# Jlink_V9.net
KiCad netlist of a schematic drawn in Altium Designer
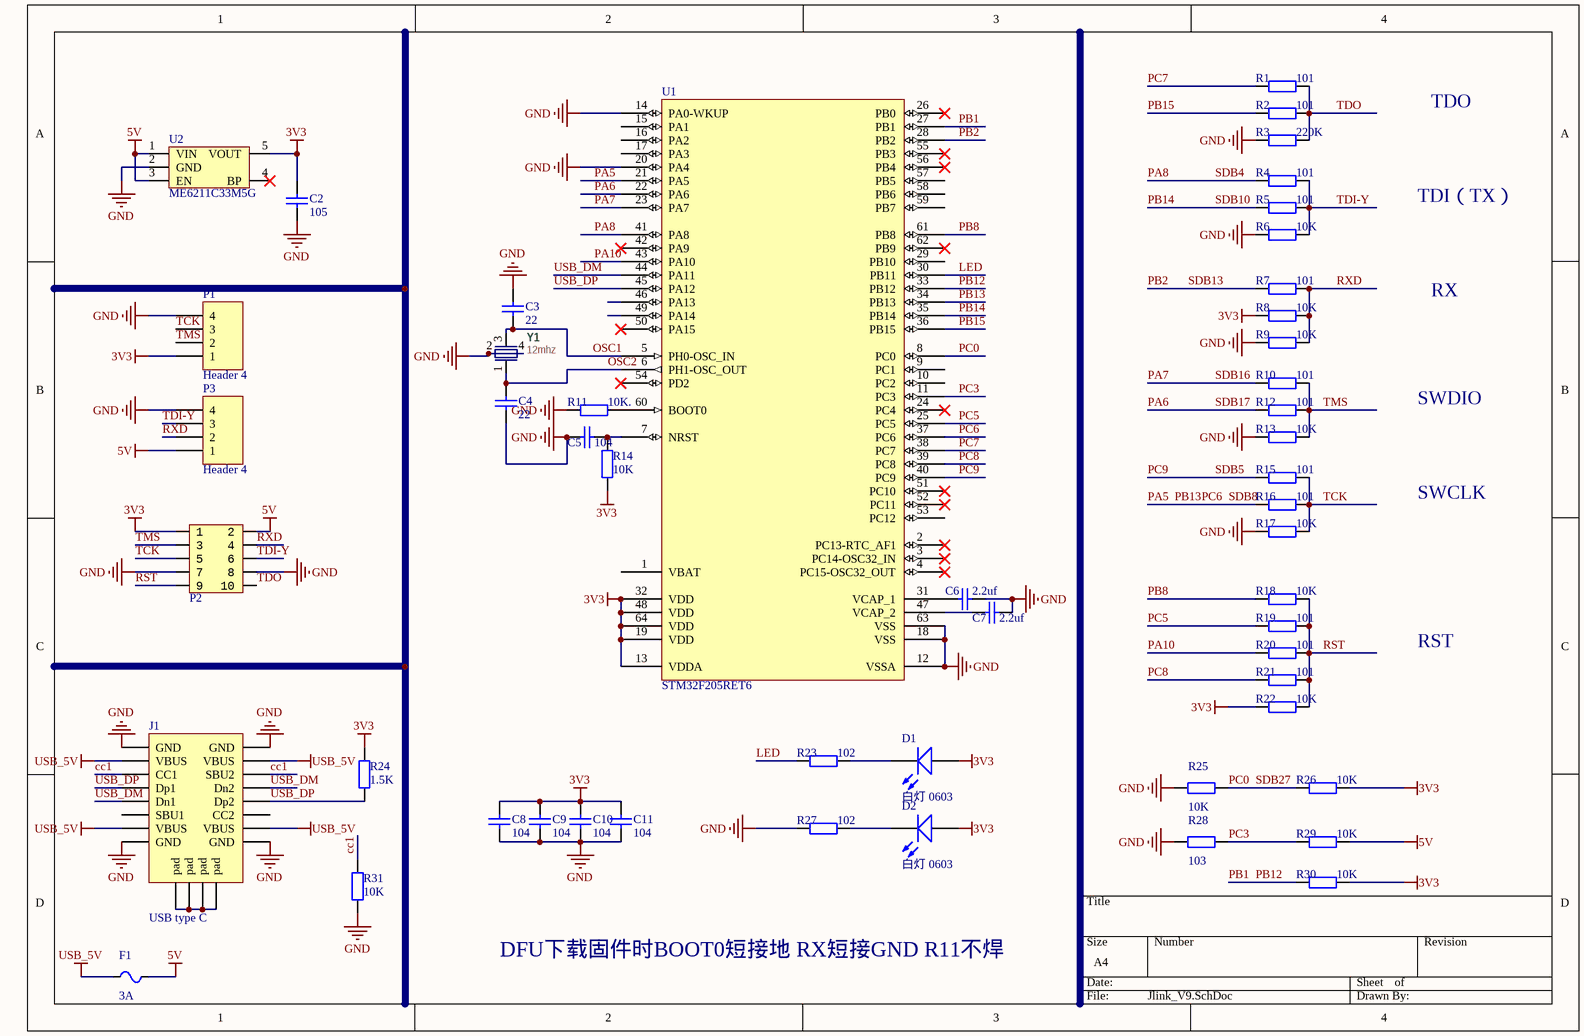
[diagram p0: Jlink_V9.SchDoc]

(export (version "E")
  (design (tool "Eeschema 10.0.6"))
  (components
    (comp (ref "C2")
      (value "105")
      (footprint "LC-0603_C")
      (description "Polarized Capacitor (Radial)")
      (fields (field (name "Comment") "104") (field (name "PUBLISHER") "Altium Limited"))
      (libsource (lib "Fantasy") (part "Cap"))
    )
    (comp (ref "C3")
      (value "22")
      (footprint "LC-0603_C")
      (description "Polarized Capacitor (Radial)")
      (fields (field (name "Comment") "104") (field (name "PUBLISHER") "Altium Limited"))
      (libsource (lib "Fantasy") (part "Cap"))
    )
    (comp (ref "C4")
      (value "22")
      (footprint "LC-0603_C")
      (description "Polarized Capacitor (Radial)")
      (fields (field (name "Comment") "104") (field (name "PUBLISHER") "Altium Limited"))
      (libsource (lib "Fantasy") (part "Cap"))
    )
    (comp (ref "C5")
      (value "104")
      (footprint "LC-0603_C")
      (description "Polarized Capacitor (Radial)")
      (fields (field (name "PUBLISHER") "Altium Limited"))
      (libsource (lib "Fantasy") (part "Cap"))
    )
    (comp (ref "C6")
      (value "2.2uf")
      (footprint "LC-0603_C")
      (description "Polarized Capacitor (Radial)")
      (fields (field (name "Comment") "2.2UF") (field (name "PUBLISHER") "Altium Limited"))
      (libsource (lib "Fantasy") (part "Cap"))
    )
    (comp (ref "C7")
      (value "2.2uf")
      (footprint "LC-0603_C")
      (description "Polarized Capacitor (Radial)")
      (fields (field (name "Comment") "2.2UF") (field (name "PUBLISHER") "Altium Limited"))
      (libsource (lib "Fantasy") (part "Cap"))
    )
    (comp (ref "C8")
      (value "104")
      (footprint "LC-0603_C")
      (description "Polarized Capacitor (Radial)")
      (fields (field (name "PUBLISHER") "Altium Limited"))
      (libsource (lib "Fantasy") (part "Cap"))
    )
    (comp (ref "C9")
      (value "104")
      (footprint "LC-0603_C")
      (description "Polarized Capacitor (Radial)")
      (fields (field (name "PUBLISHER") "Altium Limited"))
      (libsource (lib "Fantasy") (part "Cap"))
    )
    (comp (ref "C10")
      (value "104")
      (footprint "LC-0603_C")
      (description "Polarized Capacitor (Radial)")
      (fields (field (name "PUBLISHER") "Altium Limited"))
      (libsource (lib "Fantasy") (part "Cap"))
    )
    (comp (ref "C11")
      (value "104")
      (footprint "LC-0603_C")
      (description "Polarized Capacitor (Radial)")
      (fields (field (name "PUBLISHER") "Altium Limited"))
      (libsource (lib "Fantasy") (part "Cap"))
    )
    (comp (ref "D1")
      (value "白灯 0603")
      (footprint "0603_LED_S1")
      (description "发光二极管")
      (libsource (lib "Miscellaneous Devices LC") (part "0603 白灯"))
    )
    (comp (ref "D2")
      (value "白灯 0603")
      (footprint "0603_LED_S1")
      (description "发光二极管")
      (libsource (lib "Miscellaneous Devices LC") (part "0603 白灯"))
    )
    (comp (ref "F1")
      (value "3A")
      (footprint "FU 0603")
      (description "贴片保险丝")
      (fields (field (name "版权归属") "源创客"))
      (libsource (lib "IMX6UL_ALPHA(底板)_V2.0") (part "FU"))
    )
    (comp (ref "J1")
      (value "USB type C")
      (footprint "USB Type-C-16Pin_A")
      (libsource (lib "XKZ") (part "USB_C"))
    )
    (comp (ref "P1")
      (value "Header 4")
      (footprint "止痒的封装库:SMT1.25_4P-90")
      (description "Header, 4-Pin")
      (fields (field (name "PUBLISHER") "Altium Limited"))
      (libsource (lib "止痒的原理图库") (part "Header 4"))
    )
    (comp (ref "P2")
      (value "HDR2x5")
      (footprint "PCB_ConnectorHDR:HDR2X5_2.54_180HF")
      (description "Header")
      (libsource (lib "SCH_ConnectorHDR") (part "HDR2x5_2.54"))
    )
    (comp (ref "P3")
      (value "Header 4")
      (footprint "止痒的封装库:SMT1.25_4P-90")
      (description "Header, 4-Pin")
      (fields (field (name "PUBLISHER") "Altium Limited"))
      (libsource (lib "止痒的原理图库") (part "Header 4"))
    )
    (comp (ref "R1")
      (value "101")
      (footprint "LC-0603_R")
      (description "Resistor Chip")
      (fields (field (name "Comment") "100R") (field (name "PUBLISHER") "Altium Limited"))
      (libsource (lib "Fantasy") (part "Resistor"))
    )
    (comp (ref "R2")
      (value "101")
      (footprint "LC-0603_R")
      (description "Resistor Chip")
      (fields (field (name "Comment") "100R") (field (name "PUBLISHER") "Altium Limited"))
      (libsource (lib "Fantasy") (part "Resistor"))
    )
    (comp (ref "R3")
      (value "220K")
      (footprint "LC-0603_R")
      (description "Resistor Chip")
      (fields (field (name "Comment") "NC") (field (name "PUBLISHER") "Altium Limited"))
      (libsource (lib "Fantasy") (part "Resistor"))
    )
    (comp (ref "R4")
      (value "101")
      (footprint "LC-0603_R")
      (description "Resistor Chip")
      (fields (field (name "Comment") "100R") (field (name "PUBLISHER") "Altium Limited"))
      (libsource (lib "Fantasy") (part "Resistor"))
    )
    (comp (ref "R5")
      (value "101")
      (footprint "LC-0603_R")
      (description "Resistor Chip")
      (fields (field (name "Comment") "100R") (field (name "PUBLISHER") "Altium Limited"))
      (libsource (lib "Fantasy") (part "Resistor"))
    )
    (comp (ref "R6")
      (value "10K")
      (footprint "LC-0603_R")
      (description "Resistor Chip")
      (fields (field (name "PUBLISHER") "Altium Limited"))
      (libsource (lib "Fantasy") (part "Resistor"))
    )
    (comp (ref "R7")
      (value "101")
      (footprint "LC-0603_R")
      (description "Resistor Chip")
      (fields (field (name "Comment") "100R") (field (name "PUBLISHER") "Altium Limited"))
      (libsource (lib "Fantasy") (part "Resistor"))
    )
    (comp (ref "R8")
      (value "10K")
      (footprint "LC-0603_R")
      (description "Resistor Chip")
      (fields (field (name "PUBLISHER") "Altium Limited"))
      (libsource (lib "Fantasy") (part "Resistor"))
    )
    (comp (ref "R9")
      (value "10K")
      (footprint "LC-0603_R")
      (description "Resistor Chip")
      (fields (field (name "PUBLISHER") "Altium Limited"))
      (libsource (lib "Fantasy") (part "Resistor"))
    )
    (comp (ref "R10")
      (value "101")
      (footprint "LC-0603_R")
      (description "Resistor Chip")
      (fields (field (name "Comment") "100R") (field (name "PUBLISHER") "Altium Limited"))
      (libsource (lib "Fantasy") (part "Resistor"))
    )
    (comp (ref "R11")
      (value "10K.")
      (footprint "LC-0603_R")
      (description "Resistor Chip")
      (fields (field (name "Comment") "10K") (field (name "PUBLISHER") "Altium Limited"))
      (libsource (lib "Fantasy") (part "Resistor"))
    )
    (comp (ref "R12")
      (value "101")
      (footprint "LC-0603_R")
      (description "Resistor Chip")
      (fields (field (name "Comment") "100R") (field (name "PUBLISHER") "Altium Limited"))
      (libsource (lib "Fantasy") (part "Resistor"))
    )
    (comp (ref "R13")
      (value "10K")
      (footprint "LC-0603_R")
      (description "Resistor Chip")
      (fields (field (name "PUBLISHER") "Altium Limited"))
      (libsource (lib "Fantasy") (part "Resistor"))
    )
    (comp (ref "R14")
      (value "10K")
      (footprint "LC-0603_R")
      (description "Resistor Chip")
      (fields (field (name "PUBLISHER") "Altium Limited"))
      (libsource (lib "") (part "Resistor_1"))
    )
    (comp (ref "R15")
      (value "101")
      (footprint "LC-0603_R")
      (description "Resistor Chip")
      (fields (field (name "Comment") "100R") (field (name "PUBLISHER") "Altium Limited"))
      (libsource (lib "Fantasy") (part "Resistor"))
    )
    (comp (ref "R16")
      (value "101")
      (footprint "LC-0603_R")
      (description "Resistor Chip")
      (fields (field (name "Comment") "100R") (field (name "PUBLISHER") "Altium Limited"))
      (libsource (lib "Fantasy") (part "Resistor"))
    )
    (comp (ref "R17")
      (value "10K")
      (footprint "LC-0603_R")
      (description "Resistor Chip")
      (fields (field (name "PUBLISHER") "Altium Limited"))
      (libsource (lib "Fantasy") (part "Resistor"))
    )
    (comp (ref "R18")
      (value "10K")
      (footprint "LC-0603_R")
      (description "Resistor Chip")
      (fields (field (name "PUBLISHER") "Altium Limited"))
      (libsource (lib "Fantasy") (part "Resistor"))
    )
    (comp (ref "R19")
      (value "101")
      (footprint "LC-0603_R")
      (description "Resistor Chip")
      (fields (field (name "Comment") "100R") (field (name "PUBLISHER") "Altium Limited"))
      (libsource (lib "Fantasy") (part "Resistor"))
    )
    (comp (ref "R20")
      (value "101")
      (footprint "LC-0603_R")
      (description "Resistor Chip")
      (fields (field (name "Comment") "100R") (field (name "PUBLISHER") "Altium Limited"))
      (libsource (lib "Fantasy") (part "Resistor"))
    )
    (comp (ref "R21")
      (value "101")
      (footprint "LC-0603_R")
      (description "Resistor Chip")
      (fields (field (name "Comment") "10K") (field (name "PUBLISHER") "Altium Limited"))
      (libsource (lib "Fantasy") (part "Resistor"))
    )
    (comp (ref "R22")
      (value "10K")
      (footprint "LC-0603_R")
      (description "Resistor Chip")
      (fields (field (name "PUBLISHER") "Altium Limited"))
      (libsource (lib "Fantasy") (part "Resistor"))
    )
    (comp (ref "R23")
      (value "102")
      (footprint "LC-0603_R")
      (description "Resistor Chip")
      (fields (field (name "Comment") "1K") (field (name "PUBLISHER") "Altium Limited"))
      (libsource (lib "Fantasy") (part "Resistor"))
    )
    (comp (ref "R24")
      (value "1.5K")
      (footprint "LC-0603_R")
      (description "Resistor")
      (fields (field (name "PUBLISHER") "Altium Limited"))
      (libsource (lib "XKZ") (part "Res2"))
    )
    (comp (ref "R25")
      (value "10K")
      (footprint "LC-0603_R")
      (description "Resistor Chip")
      (fields (field (name "PUBLISHER") "Altium Limited"))
      (libsource (lib "Fantasy") (part "Resistor"))
    )
    (comp (ref "R26")
      (value "10K")
      (footprint "LC-0603_R")
      (description "Resistor Chip")
      (fields (field (name "PUBLISHER") "Altium Limited"))
      (libsource (lib "Fantasy") (part "Resistor"))
    )
    (comp (ref "R27")
      (value "102")
      (footprint "LC-0603_R")
      (description "Resistor Chip")
      (fields (field (name "Comment") "1K") (field (name "PUBLISHER") "Altium Limited"))
      (libsource (lib "Fantasy") (part "Resistor"))
    )
    (comp (ref "R28")
      (value "103")
      (footprint "LC-0603_R")
      (description "Resistor Chip")
      (fields (field (name "Comment") "10K") (field (name "PUBLISHER") "Altium Limited"))
      (libsource (lib "Fantasy") (part "Resistor"))
    )
    (comp (ref "R29")
      (value "10K")
      (footprint "LC-0603_R")
      (description "Resistor Chip")
      (fields (field (name "PUBLISHER") "Altium Limited"))
      (libsource (lib "Fantasy") (part "Resistor"))
    )
    (comp (ref "R30")
      (value "10K")
      (footprint "LC-0603_R")
      (description "Resistor Chip")
      (fields (field (name "PUBLISHER") "Altium Limited"))
      (libsource (lib "Fantasy") (part "Resistor"))
    )
    (comp (ref "R31")
      (value "10K")
      (footprint "LC-0603_R")
      (description "Resistor")
      (fields (field (name "PUBLISHER") "Altium Limited"))
      (libsource (lib "XKZ") (part "Res2"))
    )
    (comp (ref "U1")
      (value "STM32F205RET6")
      (footprint "LQFP64 10x10_N")
      (description "Microcontroller   ST")
      (libsource (lib "Fantasy") (part "STM32F205RET6"))
    )
    (comp (ref "U2")
      (value "ME6211C33M5G")
      (footprint "SOT23-5N")
      (description "3.3V超低压差LDO")
      (libsource (lib "Fantasy") (part "RT9193-33"))
    )
    (comp (ref "Y1")
      (value "12mhz")
      (footprint "OSC-3225")
      (description "=Description")
      (libsource (lib "止痒的原理图库") (part "XTAL"))
    )
  )
  (nets
    (net (code "1") (name "/LED") (class "Default")
      (node (ref "R23") (pin "1") (pinfunction "1_1") (pintype "passive"))
      (node (ref "U1") (pin "30") (pinfunction "PB11_30") (pintype "bidirectional"))
    )
    (net (code "2") (name "/OSC1") (class "Default")
      (node (ref "C3") (pin "1") (pinfunction "1_1") (pintype "passive"))
      (node (ref "U1") (pin "5") (pinfunction "PH0-OSC_IN_5") (pintype "input"))
      (node (ref "Y1") (pin "3") (pinfunction "3_3") (pintype "passive"))
    )
    (net (code "3") (name "/OSC2") (class "Default")
      (node (ref "C4") (pin "2") (pinfunction "2_2") (pintype "passive"))
      (node (ref "U1") (pin "6") (pinfunction "PH1-OSC_OUT_6") (pintype "output"))
      (node (ref "Y1") (pin "1") (pinfunction "1_1") (pintype "passive"))
    )
    (net (code "4") (name "/PA5") (class "Default")
      (node (ref "R16") (pin "1") (pinfunction "1_1") (pintype "passive"))
      (node (ref "U1") (pin "21") (pinfunction "PA5_21") (pintype "bidirectional"))
      (node (ref "U1") (pin "34") (pinfunction "PB13_34") (pintype "bidirectional"))
      (node (ref "U1") (pin "37") (pinfunction "PC6_37") (pintype "bidirectional"))
    )
    (net (code "5") (name "/PA6") (class "Default")
      (node (ref "R12") (pin "1") (pinfunction "1_1") (pintype "passive"))
      (node (ref "U1") (pin "22") (pinfunction "PA6_22") (pintype "bidirectional"))
    )
    (net (code "6") (name "/PA7") (class "Default")
      (node (ref "R10") (pin "1") (pinfunction "1_1") (pintype "passive"))
      (node (ref "U1") (pin "23") (pinfunction "PA7_23") (pintype "bidirectional"))
    )
    (net (code "7") (name "/PA8") (class "Default")
      (node (ref "R4") (pin "1") (pinfunction "1_1") (pintype "passive"))
      (node (ref "U1") (pin "41") (pinfunction "PA8_41") (pintype "bidirectional"))
    )
    (net (code "8") (name "/PA10") (class "Default")
      (node (ref "R20") (pin "1") (pinfunction "1_1") (pintype "passive"))
      (node (ref "U1") (pin "43") (pinfunction "PA10_43") (pintype "bidirectional"))
    )
    (net (code "9") (name "/PB1") (class "Default")
      (node (ref "R30") (pin "1") (pinfunction "1_1") (pintype "passive"))
      (node (ref "U1") (pin "27") (pinfunction "PB1_27") (pintype "bidirectional"))
      (node (ref "U1") (pin "33") (pinfunction "PB12_33") (pintype "bidirectional"))
    )
    (net (code "10") (name "/PB2") (class "Default")
      (node (ref "R7") (pin "1") (pinfunction "1_1") (pintype "passive"))
      (node (ref "U1") (pin "28") (pinfunction "PB2_28") (pintype "bidirectional"))
    )
    (net (code "11") (name "/PB8") (class "Default")
      (node (ref "R18") (pin "1") (pinfunction "1_1") (pintype "passive"))
      (node (ref "U1") (pin "61") (pinfunction "PB8_61") (pintype "bidirectional"))
    )
    (net (code "12") (name "/PB14") (class "Default")
      (node (ref "R5") (pin "1") (pinfunction "1_1") (pintype "passive"))
      (node (ref "U1") (pin "35") (pinfunction "PB14_35") (pintype "bidirectional"))
    )
    (net (code "13") (name "/PB15") (class "Default")
      (node (ref "R2") (pin "1") (pinfunction "1_1") (pintype "passive"))
      (node (ref "U1") (pin "36") (pinfunction "PB15_36") (pintype "bidirectional"))
    )
    (net (code "14") (name "/PC0") (class "Default")
      (node (ref "R25") (pin "2") (pinfunction "2_2") (pintype "passive"))
      (node (ref "R26") (pin "1") (pinfunction "1_1") (pintype "passive"))
      (node (ref "U1") (pin "8") (pinfunction "PC0_8") (pintype "bidirectional"))
    )
    (net (code "15") (name "/PC3") (class "Default")
      (node (ref "R28") (pin "2") (pinfunction "2_2") (pintype "passive"))
      (node (ref "R29") (pin "1") (pinfunction "1_1") (pintype "passive"))
      (node (ref "U1") (pin "11") (pinfunction "PC3_11") (pintype "bidirectional"))
    )
    (net (code "16") (name "/PC5") (class "Default")
      (node (ref "R19") (pin "1") (pinfunction "1_1") (pintype "passive"))
      (node (ref "U1") (pin "25") (pinfunction "PC5_25") (pintype "bidirectional"))
    )
    (net (code "17") (name "/PC7") (class "Default")
      (node (ref "R1") (pin "1") (pinfunction "1_1") (pintype "passive"))
      (node (ref "U1") (pin "38") (pinfunction "PC7_38") (pintype "bidirectional"))
    )
    (net (code "18") (name "/PC8") (class "Default")
      (node (ref "R21") (pin "1") (pinfunction "1_1") (pintype "passive"))
      (node (ref "U1") (pin "39") (pinfunction "PC8_39") (pintype "bidirectional"))
    )
    (net (code "19") (name "/PC9") (class "Default")
      (node (ref "R15") (pin "1") (pinfunction "1_1") (pintype "passive"))
      (node (ref "U1") (pin "40") (pinfunction "PC9_40") (pintype "bidirectional"))
    )
    (net (code "20") (name "/RST") (class "Default")
      (node (ref "P2") (pin "9") (pinfunction "9_9") (pintype "passive"))
      (node (ref "R18") (pin "2") (pinfunction "2_2") (pintype "passive"))
      (node (ref "R19") (pin "2") (pinfunction "2_2") (pintype "passive"))
      (node (ref "R20") (pin "2") (pinfunction "2_2") (pintype "passive"))
      (node (ref "R21") (pin "2") (pinfunction "2_2") (pintype "passive"))
      (node (ref "R22") (pin "2") (pinfunction "2_2") (pintype "passive"))
    )
    (net (code "21") (name "/RXD") (class "Default")
      (node (ref "P2") (pin "4") (pinfunction "4_4") (pintype "passive"))
      (node (ref "P3") (pin "2") (pinfunction "2_2") (pintype "passive"))
      (node (ref "R7") (pin "2") (pinfunction "2_2") (pintype "passive"))
      (node (ref "R8") (pin "2") (pinfunction "2_2") (pintype "passive"))
      (node (ref "R9") (pin "2") (pinfunction "2_2") (pintype "passive"))
    )
    (net (code "22") (name "/TCK") (class "Default")
      (node (ref "P1") (pin "3") (pinfunction "3_3") (pintype "passive"))
      (node (ref "P2") (pin "5") (pinfunction "5_5") (pintype "passive"))
      (node (ref "R15") (pin "2") (pinfunction "2_2") (pintype "passive"))
      (node (ref "R16") (pin "2") (pinfunction "2_2") (pintype "passive"))
      (node (ref "R17") (pin "2") (pinfunction "2_2") (pintype "passive"))
    )
    (net (code "23") (name "/TDI-Y") (class "Default")
      (node (ref "P2") (pin "6") (pinfunction "6_6") (pintype "passive"))
      (node (ref "P3") (pin "3") (pinfunction "3_3") (pintype "passive"))
      (node (ref "R4") (pin "2") (pinfunction "2_2") (pintype "passive"))
      (node (ref "R5") (pin "2") (pinfunction "2_2") (pintype "passive"))
      (node (ref "R6") (pin "2") (pinfunction "2_2") (pintype "passive"))
    )
    (net (code "24") (name "/TDO") (class "Default")
      (node (ref "P2") (pin "10") (pinfunction "10_10") (pintype "passive"))
      (node (ref "R1") (pin "2") (pinfunction "2_2") (pintype "passive"))
      (node (ref "R2") (pin "2") (pinfunction "2_2") (pintype "passive"))
      (node (ref "R3") (pin "2") (pinfunction "2_2") (pintype "passive"))
    )
    (net (code "25") (name "/TMS") (class "Default")
      (node (ref "P1") (pin "2") (pinfunction "2_2") (pintype "passive"))
      (node (ref "P2") (pin "3") (pinfunction "3_3") (pintype "passive"))
      (node (ref "R10") (pin "2") (pinfunction "2_2") (pintype "passive"))
      (node (ref "R12") (pin "2") (pinfunction "2_2") (pintype "passive"))
      (node (ref "R13") (pin "2") (pinfunction "2_2") (pintype "passive"))
    )
    (net (code "26") (name "/USB_DM") (class "Default")
      (node (ref "J1") (pin "A7") (pinfunction "Dn1_A7") (pintype "passive"))
      (node (ref "J1") (pin "B7") (pinfunction "Dn2_B7") (pintype "passive"))
      (node (ref "U1") (pin "44") (pinfunction "PA11_44") (pintype "bidirectional"))
    )
    (net (code "27") (name "/USB_DP") (class "Default")
      (node (ref "J1") (pin "A6") (pinfunction "Dp1_A6") (pintype "passive"))
      (node (ref "J1") (pin "B6") (pinfunction "Dp2_B6") (pintype "passive"))
      (node (ref "R24") (pin "2") (pinfunction "2_2") (pintype "passive"))
      (node (ref "U1") (pin "45") (pinfunction "PA12_45") (pintype "bidirectional"))
    )
    (net (code "28") (name "/cc1") (class "Default")
      (node (ref "J1") (pin "A5") (pinfunction "CC1_A5") (pintype "passive"))
      (node (ref "J1") (pin "B8") (pinfunction "SBU2_B8") (pintype "passive"))
      (node (ref "R31") (pin "1") (pinfunction "1_1") (pintype "passive"))
    )
    (net (code "29") (name "3V3") (class "Default")
      (node (ref "C10") (pin "2") (pinfunction "2_2") (pintype "passive"))
      (node (ref "C11") (pin "2") (pinfunction "2_2") (pintype "passive"))
      (node (ref "C2") (pin "2") (pinfunction "2_2") (pintype "passive"))
      (node (ref "C8") (pin "2") (pinfunction "2_2") (pintype "passive"))
      (node (ref "C9") (pin "2") (pinfunction "2_2") (pintype "passive"))
      (node (ref "D1") (pin "A") (pinfunction "A_A") (pintype "passive"))
      (node (ref "D2") (pin "A") (pinfunction "A_A") (pintype "passive"))
      (node (ref "P1") (pin "1") (pinfunction "1_1") (pintype "passive"))
      (node (ref "P2") (pin "1") (pinfunction "1_1") (pintype "passive"))
      (node (ref "R14") (pin "1") (pinfunction "1_1") (pintype "passive"))
      (node (ref "R22") (pin "1") (pinfunction "1_1") (pintype "passive"))
      (node (ref "R24") (pin "1") (pinfunction "1_1") (pintype "passive"))
      (node (ref "R26") (pin "2") (pinfunction "2_2") (pintype "passive"))
      (node (ref "R30") (pin "2") (pinfunction "2_2") (pintype "passive"))
      (node (ref "R8") (pin "1") (pinfunction "1_1") (pintype "passive"))
      (node (ref "U1") (pin "13") (pinfunction "VDDA_13") (pintype "power_in"))
      (node (ref "U1") (pin "19") (pinfunction "VDD_19") (pintype "power_in"))
      (node (ref "U1") (pin "32") (pinfunction "VDD_32") (pintype "power_in"))
      (node (ref "U1") (pin "48") (pinfunction "VDD_48") (pintype "power_in"))
      (node (ref "U1") (pin "64") (pinfunction "VDD_64") (pintype "power_in"))
      (node (ref "U2") (pin "5") (pinfunction "VOUT_5") (pintype "passive"))
    )
    (net (code "30") (name "5V") (class "Default")
      (node (ref "F1") (pin "2") (pinfunction "2_2") (pintype "passive"))
      (node (ref "P2") (pin "2") (pinfunction "2_2") (pintype "passive"))
      (node (ref "P3") (pin "1") (pinfunction "1_1") (pintype "passive"))
      (node (ref "R29") (pin "2") (pinfunction "2_2") (pintype "passive"))
      (node (ref "U2") (pin "1") (pinfunction "VIN_1") (pintype "passive"))
      (node (ref "U2") (pin "3") (pinfunction "EN_3") (pintype "passive"))
    )
    (net (code "31") (name "GND") (class "Default")
      (node (ref "C10") (pin "1") (pinfunction "1_1") (pintype "passive"))
      (node (ref "C11") (pin "1") (pinfunction "1_1") (pintype "passive"))
      (node (ref "C2") (pin "1") (pinfunction "1_1") (pintype "passive"))
      (node (ref "C3") (pin "2") (pinfunction "2_2") (pintype "passive"))
      (node (ref "C4") (pin "1") (pinfunction "1_1") (pintype "passive"))
      (node (ref "C5") (pin "2") (pinfunction "2_2") (pintype "passive"))
      (node (ref "C6") (pin "1") (pinfunction "1_1") (pintype "passive"))
      (node (ref "C7") (pin "1") (pinfunction "1_1") (pintype "passive"))
      (node (ref "C8") (pin "1") (pinfunction "1_1") (pintype "passive"))
      (node (ref "C9") (pin "1") (pinfunction "1_1") (pintype "passive"))
      (node (ref "J1") (pin "A1") (pinfunction "GND_A1") (pintype "passive"))
      (node (ref "J1") (pin "A12") (pinfunction "GND_A12") (pintype "passive"))
      (node (ref "J1") (pin "B1") (pinfunction "GND_B1") (pintype "passive"))
      (node (ref "J1") (pin "B12") (pinfunction "GND_B12") (pintype "passive"))
      (node (ref "P1") (pin "4") (pinfunction "4_4") (pintype "passive"))
      (node (ref "P2") (pin "7") (pinfunction "7_7") (pintype "passive"))
      (node (ref "P2") (pin "8") (pinfunction "8_8") (pintype "passive"))
      (node (ref "P3") (pin "4") (pinfunction "4_4") (pintype "passive"))
      (node (ref "R11") (pin "1") (pinfunction "1_1") (pintype "passive"))
      (node (ref "R13") (pin "1") (pinfunction "1_1") (pintype "passive"))
      (node (ref "R17") (pin "1") (pinfunction "1_1") (pintype "passive"))
      (node (ref "R25") (pin "1") (pinfunction "1_1") (pintype "passive"))
      (node (ref "R27") (pin "1") (pinfunction "1_1") (pintype "passive"))
      (node (ref "R28") (pin "1") (pinfunction "1_1") (pintype "passive"))
      (node (ref "R3") (pin "1") (pinfunction "1_1") (pintype "passive"))
      (node (ref "R31") (pin "2") (pinfunction "2_2") (pintype "passive"))
      (node (ref "R6") (pin "1") (pinfunction "1_1") (pintype "passive"))
      (node (ref "R9") (pin "1") (pinfunction "1_1") (pintype "passive"))
      (node (ref "U1") (pin "12") (pinfunction "VSSA_12") (pintype "power_in"))
      (node (ref "U1") (pin "14") (pinfunction "PA0-WKUP_14") (pintype "bidirectional"))
      (node (ref "U1") (pin "18") (pinfunction "VSS_18") (pintype "power_in"))
      (node (ref "U1") (pin "20") (pinfunction "PA4_20") (pintype "bidirectional"))
      (node (ref "U1") (pin "63") (pinfunction "VSS_63") (pintype "power_in"))
      (node (ref "U2") (pin "2") (pinfunction "GND_2") (pintype "passive"))
      (node (ref "Y1") (pin "2") (pinfunction "2_2") (pintype "passive"))
      (node (ref "Y1") (pin "4") (pinfunction "4_4") (pintype "passive"))
    )
    (net (code "32") (name "Net-(D1-PadK)") (class "Default")
      (node (ref "D1") (pin "K") (pinfunction "K_K") (pintype "passive"))
      (node (ref "R23") (pin "2") (pinfunction "2_2") (pintype "passive"))
    )
    (net (code "33") (name "Net-(D2-PadK)") (class "Default")
      (node (ref "D2") (pin "K") (pinfunction "K_K") (pintype "passive"))
      (node (ref "R27") (pin "2") (pinfunction "2_2") (pintype "passive"))
    )
    (net (code "34") (name "Net-(J1-pad)") (class "Default")
      (node (ref "J1") (pin "0") (pinfunction "pad_0") (pintype "passive"))
    )
    (net (code "35") (name "Net-(U1-BOOT0)") (class "Default")
      (node (ref "R11") (pin "2") (pinfunction "2_2") (pintype "passive"))
      (node (ref "U1") (pin "60") (pinfunction "BOOT0_60") (pintype "input"))
    )
    (net (code "36") (name "Net-(U1-NRST)") (class "Default")
      (node (ref "C5") (pin "1") (pinfunction "1_1") (pintype "passive"))
      (node (ref "R14") (pin "2") (pinfunction "2_2") (pintype "passive"))
      (node (ref "U1") (pin "7") (pinfunction "NRST_7") (pintype "bidirectional"))
    )
    (net (code "37") (name "Net-(U1-VCAP_1)") (class "Default")
      (node (ref "C6") (pin "2") (pinfunction "2_2") (pintype "passive"))
      (node (ref "U1") (pin "31") (pinfunction "VCAP_1_31") (pintype "power_in"))
    )
    (net (code "38") (name "Net-(U1-VCAP_2)") (class "Default")
      (node (ref "C7") (pin "2") (pinfunction "2_2") (pintype "passive"))
      (node (ref "U1") (pin "47") (pinfunction "VCAP_2_47") (pintype "power_in"))
    )
    (net (code "39") (name "USB_5V") (class "Default")
      (node (ref "F1") (pin "1") (pinfunction "1_1") (pintype "passive"))
      (node (ref "J1") (pin "A4") (pinfunction "VBUS_A4") (pintype "passive"))
      (node (ref "J1") (pin "A9") (pinfunction "VBUS_A9") (pintype "passive"))
      (node (ref "J1") (pin "B4") (pinfunction "VBUS_B4") (pintype "passive"))
      (node (ref "J1") (pin "B9") (pinfunction "VBUS_B9") (pintype "passive"))
    )
    (net (code "40") (name "unconnected-(J1-CC2-PadB5)") (class "Default")
      (node (ref "J1") (pin "B5") (pinfunction "CC2_B5") (pintype "passive"))
    )
    (net (code "41") (name "unconnected-(J1-SBU1-PadA8)") (class "Default")
      (node (ref "J1") (pin "A8") (pinfunction "SBU1_A8") (pintype "passive"))
    )
    (net (code "42") (name "unconnected-(U1-PA1-Pad15)") (class "Default")
      (node (ref "U1") (pin "15") (pinfunction "PA1_15") (pintype "bidirectional"))
    )
    (net (code "43") (name "unconnected-(U1-PA2-Pad16)") (class "Default")
      (node (ref "U1") (pin "16") (pinfunction "PA2_16") (pintype "bidirectional"))
    )
    (net (code "44") (name "unconnected-(U1-PA3-Pad17)") (class "Default")
      (node (ref "U1") (pin "17") (pinfunction "PA3_17") (pintype "bidirectional"))
    )
    (net (code "45") (name "unconnected-(U1-PA9-Pad42)") (class "Default")
      (node (ref "U1") (pin "42") (pinfunction "PA9_42") (pintype "bidirectional+no_connect"))
    )
    (net (code "46") (name "unconnected-(U1-PA13-Pad46)") (class "Default")
      (node (ref "U1") (pin "46") (pinfunction "PA13_46") (pintype "bidirectional"))
    )
    (net (code "47") (name "unconnected-(U1-PA14-Pad49)") (class "Default")
      (node (ref "U1") (pin "49") (pinfunction "PA14_49") (pintype "bidirectional"))
    )
    (net (code "48") (name "unconnected-(U1-PA15-Pad50)") (class "Default")
      (node (ref "U1") (pin "50") (pinfunction "PA15_50") (pintype "bidirectional+no_connect"))
    )
    (net (code "49") (name "unconnected-(U1-PB0-Pad26)") (class "Default")
      (node (ref "U1") (pin "26") (pinfunction "PB0_26") (pintype "bidirectional+no_connect"))
    )
    (net (code "50") (name "unconnected-(U1-PB3-Pad55)") (class "Default")
      (node (ref "U1") (pin "55") (pinfunction "PB3_55") (pintype "bidirectional+no_connect"))
    )
    (net (code "51") (name "unconnected-(U1-PB4-Pad56)") (class "Default")
      (node (ref "U1") (pin "56") (pinfunction "PB4_56") (pintype "bidirectional+no_connect"))
    )
    (net (code "52") (name "unconnected-(U1-PB5-Pad57)") (class "Default")
      (node (ref "U1") (pin "57") (pinfunction "PB5_57") (pintype "bidirectional"))
    )
    (net (code "53") (name "unconnected-(U1-PB6-Pad58)") (class "Default")
      (node (ref "U1") (pin "58") (pinfunction "PB6_58") (pintype "bidirectional"))
    )
    (net (code "54") (name "unconnected-(U1-PB7-Pad59)") (class "Default")
      (node (ref "U1") (pin "59") (pinfunction "PB7_59") (pintype "bidirectional"))
    )
    (net (code "55") (name "unconnected-(U1-PB9-Pad62)") (class "Default")
      (node (ref "U1") (pin "62") (pinfunction "PB9_62") (pintype "bidirectional+no_connect"))
    )
    (net (code "56") (name "unconnected-(U1-PB10-Pad29)") (class "Default")
      (node (ref "U1") (pin "29") (pinfunction "PB10_29") (pintype "bidirectional"))
    )
    (net (code "57") (name "unconnected-(U1-PC1-Pad9)") (class "Default")
      (node (ref "U1") (pin "9") (pinfunction "PC1_9") (pintype "bidirectional"))
    )
    (net (code "58") (name "unconnected-(U1-PC2-Pad10)") (class "Default")
      (node (ref "U1") (pin "10") (pinfunction "PC2_10") (pintype "bidirectional"))
    )
    (net (code "59") (name "unconnected-(U1-PC4-Pad24)") (class "Default")
      (node (ref "U1") (pin "24") (pinfunction "PC4_24") (pintype "bidirectional+no_connect"))
    )
    (net (code "60") (name "unconnected-(U1-PC10-Pad51)") (class "Default")
      (node (ref "U1") (pin "51") (pinfunction "PC10_51") (pintype "bidirectional+no_connect"))
    )
    (net (code "61") (name "unconnected-(U1-PC11-Pad52)") (class "Default")
      (node (ref "U1") (pin "52") (pinfunction "PC11_52") (pintype "bidirectional+no_connect"))
    )
    (net (code "62") (name "unconnected-(U1-PC12-Pad53)") (class "Default")
      (node (ref "U1") (pin "53") (pinfunction "PC12_53") (pintype "bidirectional"))
    )
    (net (code "63") (name "unconnected-(U1-PC13-RTC_AF1-Pad2)") (class "Default")
      (node (ref "U1") (pin "2") (pinfunction "PC13-RTC_AF1_2") (pintype "bidirectional+no_connect"))
    )
    (net (code "64") (name "unconnected-(U1-PC14-OSC32_IN-Pad3)") (class "Default")
      (node (ref "U1") (pin "3") (pinfunction "PC14-OSC32_IN_3") (pintype "bidirectional+no_connect"))
    )
    (net (code "65") (name "unconnected-(U1-PC15-OSC32_OUT-Pad4)") (class "Default")
      (node (ref "U1") (pin "4") (pinfunction "PC15-OSC32_OUT_4") (pintype "bidirectional+no_connect"))
    )
    (net (code "66") (name "unconnected-(U1-PD2-Pad54)") (class "Default")
      (node (ref "U1") (pin "54") (pinfunction "PD2_54") (pintype "bidirectional+no_connect"))
    )
    (net (code "67") (name "unconnected-(U1-VBAT-Pad1)") (class "Default")
      (node (ref "U1") (pin "1") (pinfunction "VBAT_1") (pintype "power_in"))
    )
    (net (code "68") (name "unconnected-(U2-BP-Pad4)") (class "Default")
      (node (ref "U2") (pin "4") (pinfunction "BP_4") (pintype "passive+no_connect"))
    )
  )
)
